# voltage_sensor_v0_2.net
KiCad netlist of a schematic drawn in EAGLE
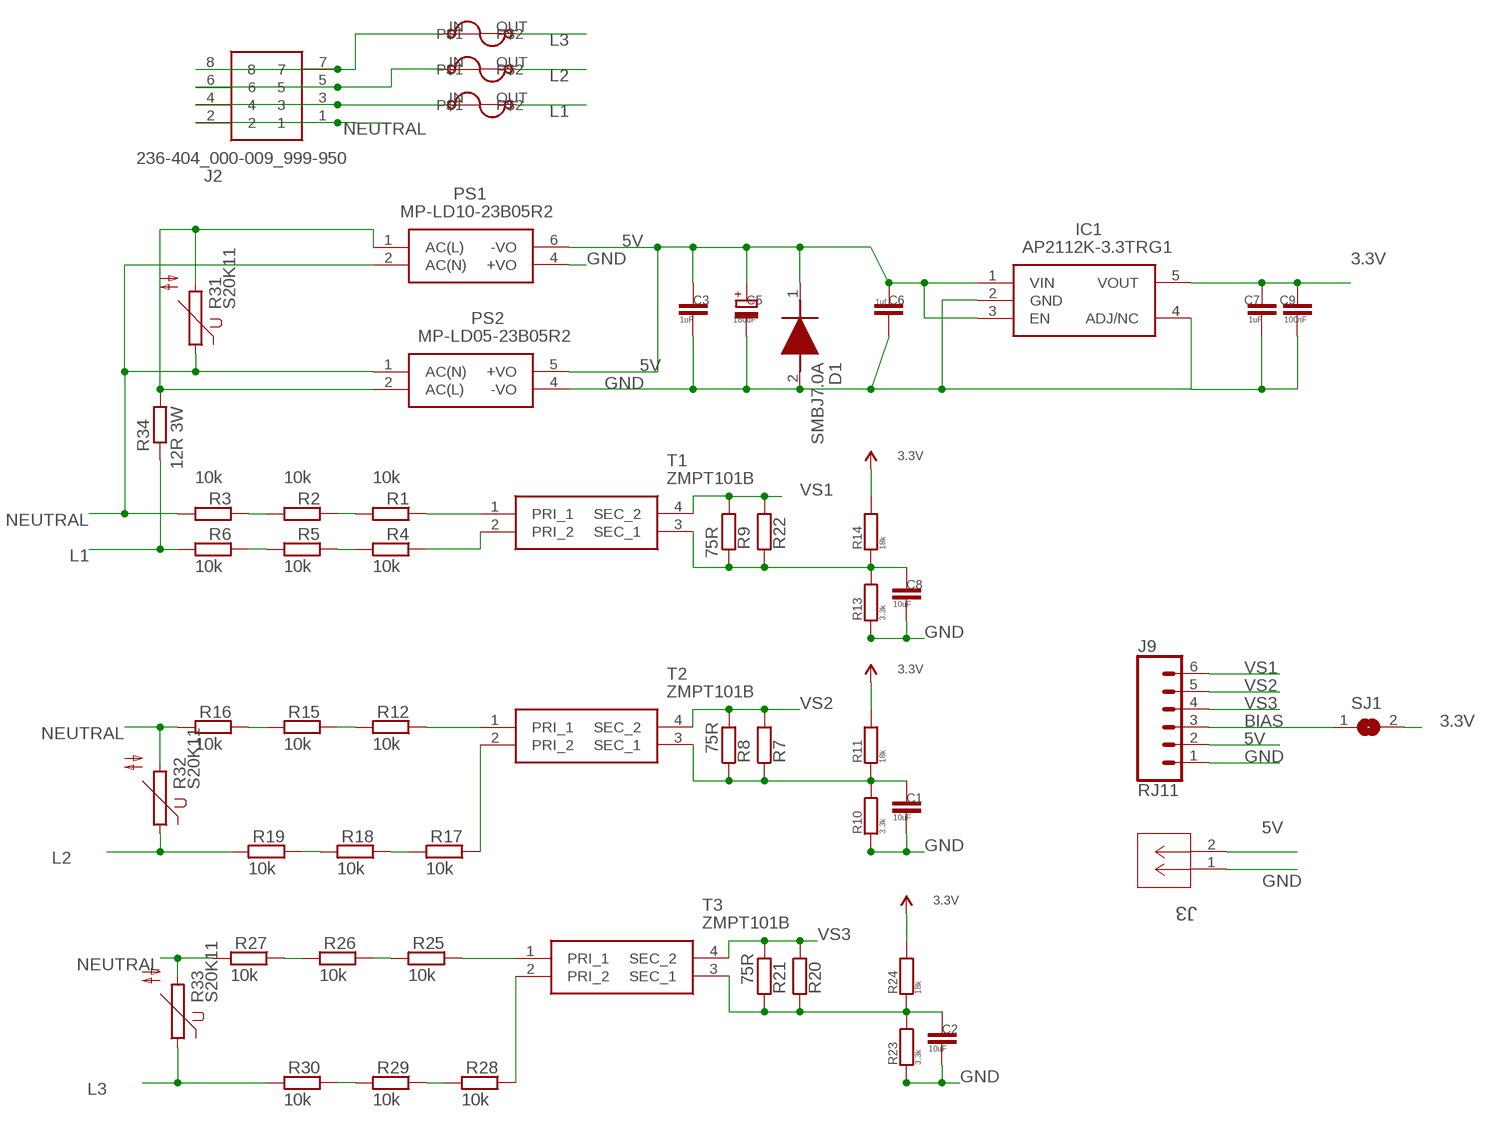
[diagram p0: schematic, sheet 1]

(export (version "E")
  (design (tool "Eeschema 10.0.6"))
  (components
    (comp (ref "C1")
      (value "10uF")
      (footprint "eagle-import:C0603")
      (libsource (lib "eagle-import") (part "C-EUC0603"))
    )
    (comp (ref "C2")
      (value "10uF")
      (footprint "eagle-import:C0603")
      (libsource (lib "eagle-import") (part "C-EUC0603"))
    )
    (comp (ref "C3")
      (value "1uF")
      (footprint "eagle-import:C0603")
      (libsource (lib "eagle-import") (part "C-EUC0603"))
    )
    (comp (ref "C5")
      (value "180uF")
      (footprint "eagle-import:PANASONIC_B")
      (libsource (lib "eagle-import") (part "CPOL-EUB"))
    )
    (comp (ref "C6")
      (value "1uf")
      (footprint "eagle-import:C0603")
      (libsource (lib "eagle-import") (part "C-EUC0603"))
    )
    (comp (ref "C7")
      (value "1uF")
      (footprint "eagle-import:C0603")
      (libsource (lib "eagle-import") (part "C-EUC0603"))
    )
    (comp (ref "C8")
      (value "10uF")
      (footprint "eagle-import:C0603")
      (libsource (lib "eagle-import") (part "C-EUC0603"))
    )
    (comp (ref "C9")
      (value "100nF")
      (footprint "eagle-import:C0603")
      (libsource (lib "eagle-import") (part "C-EUC0603"))
    )
    (comp (ref "D1")
      (value "SMBJ7.0A")
      (footprint "eagle-import:DIOM5336X244N")
      (libsource (lib "eagle-import") (part "SMBJ7.0A"))
    )
    (comp (ref "F1")
      (value "2A/250V")
      (footprint "eagle-import:BELFUSE1A")
      (libsource (lib "eagle-import") (part "BEL1AFUSE"))
    )
    (comp (ref "F2")
      (value "2A/250V")
      (footprint "eagle-import:BELFUSE1A")
      (libsource (lib "eagle-import") (part "BEL1AFUSE"))
    )
    (comp (ref "F3")
      (value "2A/250V")
      (footprint "eagle-import:BELFUSE1A")
      (libsource (lib "eagle-import") (part "BEL1AFUSE"))
    )
    (comp (ref "IC1")
      (value "AP2112K-3.3TRG1")
      (footprint "eagle-import:SOT95P282X130-5N")
      (fields (field (name "MOUSER_PART_NUMBER") "621-AP2112K-3.3TRG1"))
      (libsource (lib "eagle-import") (part "AP2112K-3.3TRG1"))
    )
    (comp (ref "J2")
      (value "236-404_000-009_999-950")
      (footprint "eagle-import:236404000009999950")
      (fields
        (field (name "ARROW_PART_NUMBER") "236-404/000-009/999-950")
        (field (name "ARROW_PART_NUMBER_1") "J2")
      )
      (libsource (lib "eagle-import") (part "236-404_000-009_999-950"))
    )
    (comp (ref "J3")
      (value "MC000048")
      (footprint "eagle-import:CONN2_00048_MTC")
      (fields (field (name "COPYRIGHT") "Copyright (C) 2022 Ultra Librarian. All rights reserved."))
      (libsource (lib "eagle-import") (part "MC000048"))
    )
    (comp (ref "J9")
      (value "RJ11")
      (footprint "eagle-import:RJ11-6")
      (libsource (lib "eagle-import") (part "RJ11-6"))
    )
    (comp (ref "PS1")
      (value "MP-LD10-23B05R2")
      (footprint "eagle-import:MPLD1023B12R2")
      (libsource (lib "eagle-import") (part "MP-LD10-23B12R2"))
    )
    (comp (ref "PS2")
      (value "MP-LD05-23B05R2")
      (footprint "eagle-import:MPLD0523B03R2")
      (fields (field (name "MANUFACTURER_PART_NUMBER") "MP-LD05-23B03R2"))
      (libsource (lib "eagle-import") (part "MP-LD05-23B03R2"))
    )
    (comp (ref "R1")
      (value "10k")
      (footprint "eagle-import:R0603")
      (libsource (lib "eagle-import") (part "R-EU_R0603"))
    )
    (comp (ref "R2")
      (value "10k")
      (footprint "eagle-import:R0603")
      (libsource (lib "eagle-import") (part "R-EU_R0603"))
    )
    (comp (ref "R3")
      (value "10k")
      (footprint "eagle-import:R0603")
      (libsource (lib "eagle-import") (part "R-EU_R0603"))
    )
    (comp (ref "R4")
      (value "10k")
      (footprint "eagle-import:R0603")
      (libsource (lib "eagle-import") (part "R-EU_R0603"))
    )
    (comp (ref "R5")
      (value "10k")
      (footprint "eagle-import:R0603")
      (libsource (lib "eagle-import") (part "R-EU_R0603"))
    )
    (comp (ref "R6")
      (value "10k")
      (footprint "eagle-import:R0603")
      (libsource (lib "eagle-import") (part "R-EU_R0603"))
    )
    (comp (ref "R7")
      (value "R-EU_0204/7")
      (footprint "eagle-import:0204_7")
      (libsource (lib "eagle-import") (part "R-EU_0204/7"))
    )
    (comp (ref "R8")
      (value "75R")
      (footprint "eagle-import:R0603")
      (libsource (lib "eagle-import") (part "R-EU_R0603"))
    )
    (comp (ref "R9")
      (value "75R")
      (footprint "eagle-import:R0603")
      (libsource (lib "eagle-import") (part "R-EU_R0603"))
    )
    (comp (ref "R10")
      (value "3.3k")
      (footprint "eagle-import:R0603")
      (libsource (lib "eagle-import") (part "R-EU_R0603"))
    )
    (comp (ref "R11")
      (value "18k")
      (footprint "eagle-import:R0603")
      (libsource (lib "eagle-import") (part "R-EU_R0603"))
    )
    (comp (ref "R12")
      (value "10k")
      (footprint "eagle-import:R0603")
      (libsource (lib "eagle-import") (part "R-EU_R0603"))
    )
    (comp (ref "R13")
      (value "3.3k")
      (footprint "eagle-import:R0603")
      (libsource (lib "eagle-import") (part "R-EU_R0603"))
    )
    (comp (ref "R14")
      (value "18k")
      (footprint "eagle-import:R0603")
      (libsource (lib "eagle-import") (part "R-EU_R0603"))
    )
    (comp (ref "R15")
      (value "10k")
      (footprint "eagle-import:R0603")
      (libsource (lib "eagle-import") (part "R-EU_R0603"))
    )
    (comp (ref "R16")
      (value "10k")
      (footprint "eagle-import:R0603")
      (libsource (lib "eagle-import") (part "R-EU_R0603"))
    )
    (comp (ref "R17")
      (value "10k")
      (footprint "eagle-import:R0603")
      (libsource (lib "eagle-import") (part "R-EU_R0603"))
    )
    (comp (ref "R18")
      (value "10k")
      (footprint "eagle-import:R0603")
      (libsource (lib "eagle-import") (part "R-EU_R0603"))
    )
    (comp (ref "R19")
      (value "10k")
      (footprint "eagle-import:R0603")
      (libsource (lib "eagle-import") (part "R-EU_R0603"))
    )
    (comp (ref "R20")
      (value "R-EU_0204/7")
      (footprint "eagle-import:0204_7")
      (libsource (lib "eagle-import") (part "R-EU_0204/7"))
    )
    (comp (ref "R21")
      (value "75R")
      (footprint "eagle-import:R0603")
      (libsource (lib "eagle-import") (part "R-EU_R0603"))
    )
    (comp (ref "R22")
      (value "R-EU_0204/7")
      (footprint "eagle-import:0204_7")
      (libsource (lib "eagle-import") (part "R-EU_0204/7"))
    )
    (comp (ref "R23")
      (value "3.3k")
      (footprint "eagle-import:R0603")
      (libsource (lib "eagle-import") (part "R-EU_R0603"))
    )
    (comp (ref "R24")
      (value "18k")
      (footprint "eagle-import:R0603")
      (libsource (lib "eagle-import") (part "R-EU_R0603"))
    )
    (comp (ref "R25")
      (value "10k")
      (footprint "eagle-import:R0603")
      (libsource (lib "eagle-import") (part "R-EU_R0603"))
    )
    (comp (ref "R26")
      (value "10k")
      (footprint "eagle-import:R0603")
      (libsource (lib "eagle-import") (part "R-EU_R0603"))
    )
    (comp (ref "R27")
      (value "10k")
      (footprint "eagle-import:R0603")
      (libsource (lib "eagle-import") (part "R-EU_R0603"))
    )
    (comp (ref "R28")
      (value "10k")
      (footprint "eagle-import:R0603")
      (libsource (lib "eagle-import") (part "R-EU_R0603"))
    )
    (comp (ref "R29")
      (value "10k")
      (footprint "eagle-import:R0603")
      (libsource (lib "eagle-import") (part "R-EU_R0603"))
    )
    (comp (ref "R30")
      (value "10k")
      (footprint "eagle-import:R0603")
      (libsource (lib "eagle-import") (part "R-EU_R0603"))
    )
    (comp (ref "R31")
      (value "S20K11")
      (footprint "eagle-import:S20K11")
      (libsource (lib "eagle-import") (part "S20K11"))
    )
    (comp (ref "R32")
      (value "S20K11")
      (footprint "eagle-import:S20K11")
      (libsource (lib "eagle-import") (part "S20K11"))
    )
    (comp (ref "R33")
      (value "S20K11")
      (footprint "eagle-import:S20K11")
      (libsource (lib "eagle-import") (part "S20K11"))
    )
    (comp (ref "R34")
      (value "12R 3W")
      (footprint "eagle-import:R2512")
      (libsource (lib "eagle-import") (part "rcl_334_R-EU_R2512"))
    )
    (comp (ref "SJ1") (value "SJ") (footprint "eagle-import:SJ") (libsource (lib "eagle-import") (part "SJ")))
    (comp (ref "T1")
      (value "ZMPT101B")
      (footprint "eagle-import:ZMPT101B")
      (libsource (lib "eagle-import") (part "ZMPT101B"))
    )
    (comp (ref "T2")
      (value "ZMPT101B")
      (footprint "eagle-import:ZMPT101B")
      (libsource (lib "eagle-import") (part "ZMPT101B"))
    )
    (comp (ref "T3")
      (value "ZMPT101B")
      (footprint "eagle-import:ZMPT101B")
      (libsource (lib "eagle-import") (part "ZMPT101B"))
    )
  )
  (nets
    (net (code "1") (name "/5V") (class "Default")
      (node (ref "C3") (pin "1") (pinfunction "1_1") (pintype "passive"))
      (node (ref "C5") (pin "+") (pinfunction "+_+") (pintype "passive"))
      (node (ref "C6") (pin "1") (pinfunction "1_1") (pintype "passive"))
      (node (ref "D1") (pin "1") (pinfunction "K_1") (pintype "bidirectional"))
      (node (ref "IC1") (pin "1") (pinfunction "VIN_1") (pintype "bidirectional"))
      (node (ref "IC1") (pin "3") (pinfunction "EN_3") (pintype "bidirectional"))
      (node (ref "J3") (pin "2") (pinfunction "2_2") (pintype "passive"))
      (node (ref "J9") (pin "2") (pinfunction "2_2") (pintype "passive"))
      (node (ref "PS1") (pin "6") (pinfunction "-VO_6") (pintype "bidirectional"))
      (node (ref "PS2") (pin "5") (pinfunction "+VO_5") (pintype "bidirectional"))
    )
    (net (code "2") (name "/BIAS") (class "Default")
      (node (ref "J9") (pin "3") (pinfunction "3_3") (pintype "passive"))
      (node (ref "SJ1") (pin "1") (pinfunction "1_1") (pintype "passive"))
    )
    (net (code "3") (name "/GND") (class "Default")
      (node (ref "C1") (pin "2") (pinfunction "2_2") (pintype "passive"))
      (node (ref "C2") (pin "2") (pinfunction "2_2") (pintype "passive"))
      (node (ref "C3") (pin "2") (pinfunction "2_2") (pintype "passive"))
      (node (ref "C5") (pin "-") (pinfunction "-_-") (pintype "passive"))
      (node (ref "C6") (pin "2") (pinfunction "2_2") (pintype "passive"))
      (node (ref "C7") (pin "2") (pinfunction "2_2") (pintype "passive"))
      (node (ref "C8") (pin "2") (pinfunction "2_2") (pintype "passive"))
      (node (ref "C9") (pin "2") (pinfunction "2_2") (pintype "passive"))
      (node (ref "D1") (pin "2") (pinfunction "A_2") (pintype "bidirectional"))
      (node (ref "IC1") (pin "2") (pinfunction "GND_2") (pintype "bidirectional"))
      (node (ref "IC1") (pin "4") (pinfunction "ADJ/NC_4") (pintype "bidirectional"))
      (node (ref "J3") (pin "1") (pinfunction "1_1") (pintype "passive"))
      (node (ref "J9") (pin "1") (pinfunction "1_1") (pintype "passive"))
      (node (ref "PS1") (pin "4") (pinfunction "+VO_4") (pintype "bidirectional"))
      (node (ref "PS2") (pin "4") (pinfunction "-VO_4") (pintype "bidirectional"))
      (node (ref "R10") (pin "2") (pinfunction "2_2") (pintype "passive"))
      (node (ref "R13") (pin "2") (pinfunction "2_2") (pintype "passive"))
      (node (ref "R23") (pin "2") (pinfunction "2_2") (pintype "passive"))
    )
    (net (code "4") (name "/L1") (class "Default")
      (node (ref "F1") (pin "OUT") (pinfunction "P$1_OUT") (pintype "bidirectional"))
      (node (ref "R34") (pin "1") (pinfunction "1_1") (pintype "passive"))
      (node (ref "R6") (pin "2") (pinfunction "2_2") (pintype "passive"))
    )
    (net (code "5") (name "/L2") (class "Default")
      (node (ref "F2") (pin "OUT") (pinfunction "P$1_OUT") (pintype "bidirectional"))
      (node (ref "R19") (pin "2") (pinfunction "2_2") (pintype "passive"))
      (node (ref "R32") (pin "1") (pinfunction "1_1") (pintype "passive"))
    )
    (net (code "6") (name "/L3") (class "Default")
      (node (ref "F3") (pin "OUT") (pinfunction "P$1_OUT") (pintype "bidirectional"))
      (node (ref "R30") (pin "2") (pinfunction "2_2") (pintype "passive"))
      (node (ref "R33") (pin "1") (pinfunction "1_1") (pintype "passive"))
    )
    (net (code "7") (name "/NEUTRAL") (class "Default")
      (node (ref "J2") (pin "1") (pinfunction "1_1") (pintype "bidirectional"))
      (node (ref "J2") (pin "2") (pinfunction "2_2") (pintype "bidirectional"))
      (node (ref "PS1") (pin "2") (pinfunction "AC(N)_2") (pintype "bidirectional"))
      (node (ref "PS2") (pin "1") (pinfunction "AC(N)_1") (pintype "bidirectional"))
      (node (ref "R16") (pin "2") (pinfunction "2_2") (pintype "passive"))
      (node (ref "R27") (pin "2") (pinfunction "2_2") (pintype "passive"))
      (node (ref "R3") (pin "2") (pinfunction "2_2") (pintype "passive"))
      (node (ref "R31") (pin "1") (pinfunction "1_1") (pintype "passive"))
      (node (ref "R32") (pin "2") (pinfunction "2_2") (pintype "passive"))
      (node (ref "R33") (pin "2") (pinfunction "2_2") (pintype "passive"))
    )
    (net (code "8") (name "/VS1") (class "Default")
      (node (ref "J9") (pin "6") (pinfunction "6_6") (pintype "passive"))
      (node (ref "R22") (pin "2") (pinfunction "2_2") (pintype "passive"))
      (node (ref "R9") (pin "2") (pinfunction "2_2") (pintype "passive"))
      (node (ref "T1") (pin "4") (pinfunction "SEC_2_4") (pintype "bidirectional"))
    )
    (net (code "9") (name "/VS2") (class "Default")
      (node (ref "J9") (pin "5") (pinfunction "5_5") (pintype "passive"))
      (node (ref "R7") (pin "2") (pinfunction "2_2") (pintype "passive"))
      (node (ref "R8") (pin "2") (pinfunction "2_2") (pintype "passive"))
      (node (ref "T2") (pin "4") (pinfunction "SEC_2_4") (pintype "bidirectional"))
    )
    (net (code "10") (name "/VS3") (class "Default")
      (node (ref "J9") (pin "4") (pinfunction "4_4") (pintype "passive"))
      (node (ref "R20") (pin "2") (pinfunction "2_2") (pintype "passive"))
      (node (ref "R21") (pin "2") (pinfunction "2_2") (pintype "passive"))
      (node (ref "T3") (pin "4") (pinfunction "SEC_2_4") (pintype "bidirectional"))
    )
    (net (code "11") (name "3.3V") (class "Default")
      (node (ref "C7") (pin "1") (pinfunction "1_1") (pintype "passive"))
      (node (ref "C9") (pin "1") (pinfunction "1_1") (pintype "passive"))
      (node (ref "IC1") (pin "5") (pinfunction "VOUT_5") (pintype "bidirectional"))
      (node (ref "R11") (pin "2") (pinfunction "2_2") (pintype "passive"))
      (node (ref "R14") (pin "2") (pinfunction "2_2") (pintype "passive"))
      (node (ref "R24") (pin "2") (pinfunction "2_2") (pintype "passive"))
      (node (ref "SJ1") (pin "2") (pinfunction "2_2") (pintype "passive"))
    )
    (net (code "12") (name "Net-(F1-P$2)") (class "Default")
      (node (ref "F1") (pin "IN") (pinfunction "P$2_IN") (pintype "bidirectional"))
      (node (ref "J2") (pin "3") (pinfunction "3_3") (pintype "bidirectional"))
      (node (ref "J2") (pin "4") (pinfunction "4_4") (pintype "bidirectional"))
    )
    (net (code "13") (name "Net-(F2-P$2)") (class "Default")
      (node (ref "F2") (pin "IN") (pinfunction "P$2_IN") (pintype "bidirectional"))
      (node (ref "J2") (pin "5") (pinfunction "5_5") (pintype "bidirectional"))
      (node (ref "J2") (pin "6") (pinfunction "6_6") (pintype "bidirectional"))
    )
    (net (code "14") (name "Net-(F3-P$2)") (class "Default")
      (node (ref "F3") (pin "IN") (pinfunction "P$2_IN") (pintype "bidirectional"))
      (node (ref "J2") (pin "7") (pinfunction "7_7") (pintype "bidirectional"))
      (node (ref "J2") (pin "8") (pinfunction "8_8") (pintype "bidirectional"))
    )
    (net (code "15") (name "Net-(PS1-AC(L))") (class "Default")
      (node (ref "PS1") (pin "1") (pinfunction "AC(L)_1") (pintype "bidirectional"))
      (node (ref "PS2") (pin "2") (pinfunction "AC(L)_2") (pintype "bidirectional"))
      (node (ref "R31") (pin "2") (pinfunction "2_2") (pintype "passive"))
      (node (ref "R34") (pin "2") (pinfunction "2_2") (pintype "passive"))
    )
    (net (code "16") (name "Net-(R1-Pad2)") (class "Default")
      (node (ref "R1") (pin "2") (pinfunction "2_2") (pintype "passive"))
      (node (ref "R2") (pin "1") (pinfunction "1_1") (pintype "passive"))
    )
    (net (code "17") (name "Net-(R2-Pad2)") (class "Default")
      (node (ref "R2") (pin "2") (pinfunction "2_2") (pintype "passive"))
      (node (ref "R3") (pin "1") (pinfunction "1_1") (pintype "passive"))
    )
    (net (code "18") (name "Net-(R4-Pad2)") (class "Default")
      (node (ref "R4") (pin "2") (pinfunction "2_2") (pintype "passive"))
      (node (ref "R5") (pin "1") (pinfunction "1_1") (pintype "passive"))
    )
    (net (code "19") (name "Net-(R5-Pad2)") (class "Default")
      (node (ref "R5") (pin "2") (pinfunction "2_2") (pintype "passive"))
      (node (ref "R6") (pin "1") (pinfunction "1_1") (pintype "passive"))
    )
    (net (code "20") (name "Net-(R12-Pad2)") (class "Default")
      (node (ref "R12") (pin "2") (pinfunction "2_2") (pintype "passive"))
      (node (ref "R15") (pin "1") (pinfunction "1_1") (pintype "passive"))
    )
    (net (code "21") (name "Net-(R15-Pad2)") (class "Default")
      (node (ref "R15") (pin "2") (pinfunction "2_2") (pintype "passive"))
      (node (ref "R16") (pin "1") (pinfunction "1_1") (pintype "passive"))
    )
    (net (code "22") (name "Net-(R17-Pad2)") (class "Default")
      (node (ref "R17") (pin "2") (pinfunction "2_2") (pintype "passive"))
      (node (ref "R18") (pin "1") (pinfunction "1_1") (pintype "passive"))
    )
    (net (code "23") (name "Net-(R18-Pad2)") (class "Default")
      (node (ref "R18") (pin "2") (pinfunction "2_2") (pintype "passive"))
      (node (ref "R19") (pin "1") (pinfunction "1_1") (pintype "passive"))
    )
    (net (code "24") (name "Net-(R25-Pad2)") (class "Default")
      (node (ref "R25") (pin "2") (pinfunction "2_2") (pintype "passive"))
      (node (ref "R26") (pin "1") (pinfunction "1_1") (pintype "passive"))
    )
    (net (code "25") (name "Net-(R26-Pad2)") (class "Default")
      (node (ref "R26") (pin "2") (pinfunction "2_2") (pintype "passive"))
      (node (ref "R27") (pin "1") (pinfunction "1_1") (pintype "passive"))
    )
    (net (code "26") (name "Net-(R28-Pad2)") (class "Default")
      (node (ref "R28") (pin "2") (pinfunction "2_2") (pintype "passive"))
      (node (ref "R29") (pin "1") (pinfunction "1_1") (pintype "passive"))
    )
    (net (code "27") (name "Net-(R29-Pad2)") (class "Default")
      (node (ref "R29") (pin "2") (pinfunction "2_2") (pintype "passive"))
      (node (ref "R30") (pin "1") (pinfunction "1_1") (pintype "passive"))
    )
    (net (code "28") (name "Net-(T1-PRI_1)") (class "Default")
      (node (ref "R1") (pin "1") (pinfunction "1_1") (pintype "passive"))
      (node (ref "T1") (pin "1") (pinfunction "PRI_1_1") (pintype "bidirectional"))
    )
    (net (code "29") (name "Net-(T1-PRI_2)") (class "Default")
      (node (ref "R4") (pin "1") (pinfunction "1_1") (pintype "passive"))
      (node (ref "T1") (pin "2") (pinfunction "PRI_2_2") (pintype "bidirectional"))
    )
    (net (code "30") (name "Net-(T1-SEC_1)") (class "Default")
      (node (ref "C8") (pin "1") (pinfunction "1_1") (pintype "passive"))
      (node (ref "R13") (pin "1") (pinfunction "1_1") (pintype "passive"))
      (node (ref "R14") (pin "1") (pinfunction "1_1") (pintype "passive"))
      (node (ref "R22") (pin "1") (pinfunction "1_1") (pintype "passive"))
      (node (ref "R9") (pin "1") (pinfunction "1_1") (pintype "passive"))
      (node (ref "T1") (pin "3") (pinfunction "SEC_1_3") (pintype "bidirectional"))
    )
    (net (code "31") (name "Net-(T2-PRI_1)") (class "Default")
      (node (ref "R12") (pin "1") (pinfunction "1_1") (pintype "passive"))
      (node (ref "T2") (pin "1") (pinfunction "PRI_1_1") (pintype "bidirectional"))
    )
    (net (code "32") (name "Net-(T2-PRI_2)") (class "Default")
      (node (ref "R17") (pin "1") (pinfunction "1_1") (pintype "passive"))
      (node (ref "T2") (pin "2") (pinfunction "PRI_2_2") (pintype "bidirectional"))
    )
    (net (code "33") (name "Net-(T2-SEC_1)") (class "Default")
      (node (ref "C1") (pin "1") (pinfunction "1_1") (pintype "passive"))
      (node (ref "R10") (pin "1") (pinfunction "1_1") (pintype "passive"))
      (node (ref "R11") (pin "1") (pinfunction "1_1") (pintype "passive"))
      (node (ref "R7") (pin "1") (pinfunction "1_1") (pintype "passive"))
      (node (ref "R8") (pin "1") (pinfunction "1_1") (pintype "passive"))
      (node (ref "T2") (pin "3") (pinfunction "SEC_1_3") (pintype "bidirectional"))
    )
    (net (code "34") (name "Net-(T3-PRI_1)") (class "Default")
      (node (ref "R25") (pin "1") (pinfunction "1_1") (pintype "passive"))
      (node (ref "T3") (pin "1") (pinfunction "PRI_1_1") (pintype "bidirectional"))
    )
    (net (code "35") (name "Net-(T3-PRI_2)") (class "Default")
      (node (ref "R28") (pin "1") (pinfunction "1_1") (pintype "passive"))
      (node (ref "T3") (pin "2") (pinfunction "PRI_2_2") (pintype "bidirectional"))
    )
    (net (code "36") (name "Net-(T3-SEC_1)") (class "Default")
      (node (ref "C2") (pin "1") (pinfunction "1_1") (pintype "passive"))
      (node (ref "R20") (pin "1") (pinfunction "1_1") (pintype "passive"))
      (node (ref "R21") (pin "1") (pinfunction "1_1") (pintype "passive"))
      (node (ref "R23") (pin "1") (pinfunction "1_1") (pintype "passive"))
      (node (ref "R24") (pin "1") (pinfunction "1_1") (pintype "passive"))
      (node (ref "T3") (pin "3") (pinfunction "SEC_1_3") (pintype "bidirectional"))
    )
  )
)
